# SparkFun_Digi_XBee_Explorer_USB-C.net
KiCad netlist of a schematic drawn in EAGLE
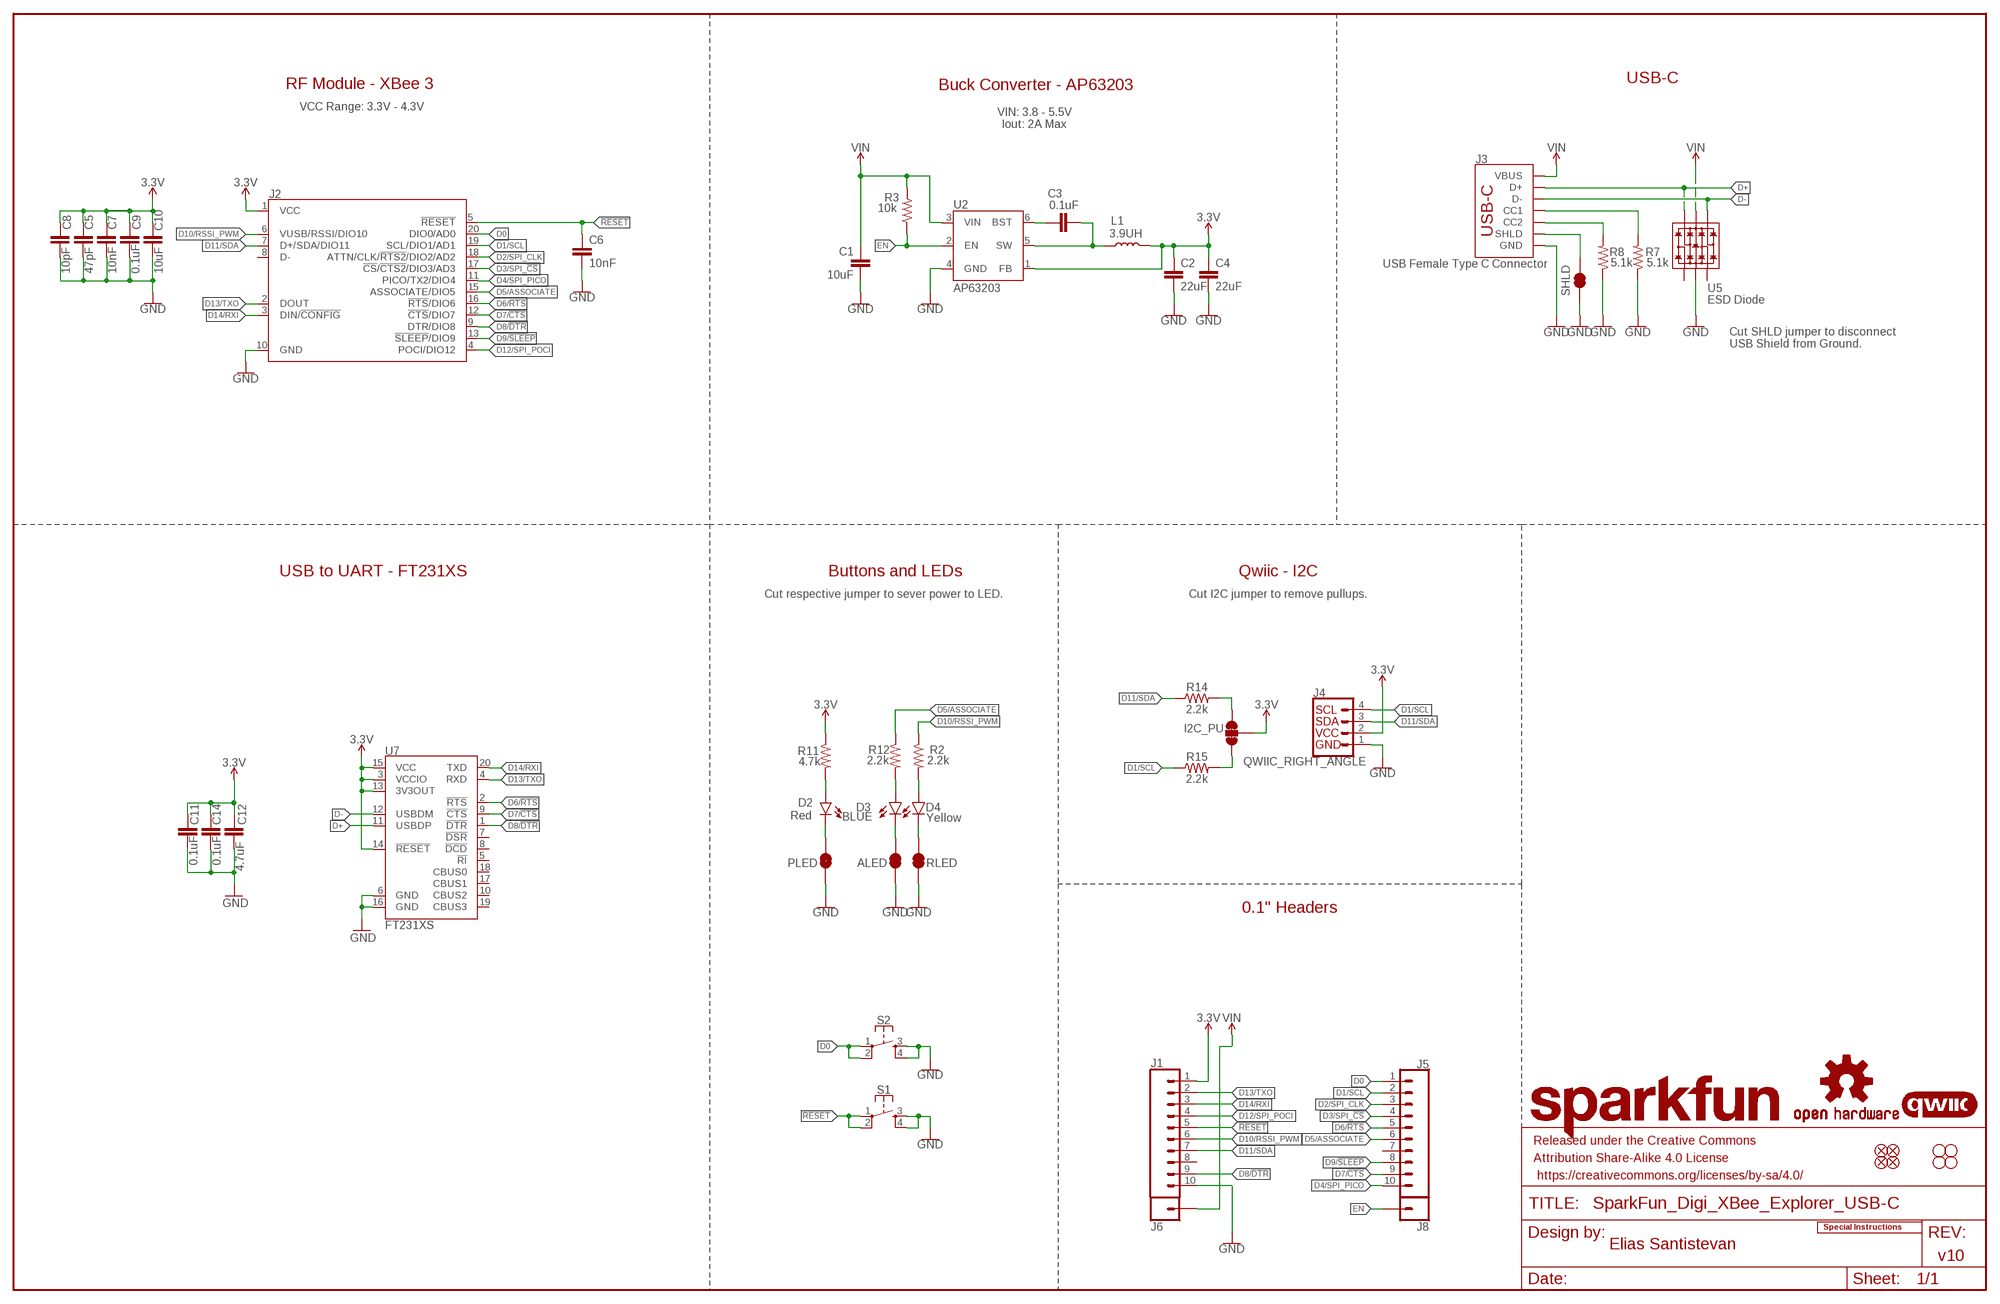
[diagram p0: schematic, sheet 1]

(export (version "E")
  (design (tool "Eeschema 10.0.6"))
  (components
    (comp (ref "ALED")
      (value "JUMPER-SMT_2_NC_TRACE_SILK")
      (footprint "eagle-import:SMT-JUMPER_2_NC_TRACE_SILK")
      (libsource (lib "eagle-import") (part "JUMPER-SMT_2_NC_TRACE_SILK"))
    )
    (comp (ref "C1")
      (value "10uF")
      (footprint "eagle-import:1210")
      (libsource (lib "eagle-import") (part "10UF-1210-50V-20%"))
    )
    (comp (ref "C2")
      (value "22uF")
      (footprint "eagle-import:0603")
      (libsource (lib "eagle-import") (part "22UF-0603-6.3V-20%"))
    )
    (comp (ref "C3")
      (value "0.1uF")
      (footprint "eagle-import:0603")
      (libsource (lib "eagle-import") (part "0.1UF-0603-25V-5%"))
    )
    (comp (ref "C4")
      (value "22uF")
      (footprint "eagle-import:0603")
      (libsource (lib "eagle-import") (part "22UF-0603-6.3V-20%"))
    )
    (comp (ref "C5")
      (value "47pF")
      (footprint "eagle-import:0603")
      (libsource (lib "eagle-import") (part "47PF-0603-50V-5%"))
    )
    (comp (ref "C6")
      (value "10nF")
      (footprint "eagle-import:0603")
      (libsource (lib "eagle-import") (part "10NF-0603-50V-10%"))
    )
    (comp (ref "C7")
      (value "10nF")
      (footprint "eagle-import:0603")
      (libsource (lib "eagle-import") (part "10NF-0603-50V-10%"))
    )
    (comp (ref "C8")
      (value "10pF")
      (footprint "eagle-import:0603")
      (libsource (lib "eagle-import") (part "10PF-0603-50V-5%"))
    )
    (comp (ref "C9")
      (value "0.1uF")
      (footprint "eagle-import:0603")
      (libsource (lib "eagle-import") (part "0.1UF-0603-25V-(+80/-20%)"))
    )
    (comp (ref "C10")
      (value "10uF")
      (footprint "eagle-import:0603")
      (libsource (lib "eagle-import") (part "10UF-0603-6.3V-20%"))
    )
    (comp (ref "C11")
      (value "0.1uF")
      (footprint "eagle-import:0603")
      (libsource (lib "eagle-import") (part "0.1UF-0603-25V-(+80/-20%)"))
    )
    (comp (ref "C12")
      (value "4.7uF")
      (footprint "eagle-import:0603")
      (libsource (lib "eagle-import") (part "4.7UF-0603-6.3V-(10%)"))
    )
    (comp (ref "C14")
      (value "0.1uF")
      (footprint "eagle-import:0603")
      (libsource (lib "eagle-import") (part "0.1UF-0603-25V-(+80/-20%)"))
    )
    (comp (ref "D2")
      (value "Red")
      (footprint "eagle-import:LED-0603")
      (libsource (lib "eagle-import") (part "LED-RED_0603-KB"))
    )
    (comp (ref "D3")
      (value "BLUE")
      (footprint "eagle-import:LED-0603")
      (libsource (lib "eagle-import") (part "LED-BLUE0603"))
    )
    (comp (ref "D4")
      (value "Yellow")
      (footprint "eagle-import:LED-0603")
      (libsource (lib "eagle-import") (part "LED-YELLOW0603"))
    )
    (comp (ref "FD1")
      (value "FIDUCIAL1X2")
      (footprint "eagle-import:FIDUCIAL-1X2")
      (libsource (lib "eagle-import") (part "FIDUCIAL1X2"))
    )
    (comp (ref "FD2")
      (value "FIDUCIAL1X2")
      (footprint "eagle-import:FIDUCIAL-1X2")
      (libsource (lib "eagle-import") (part "FIDUCIAL1X2"))
    )
    (comp (ref "FD3")
      (value "FIDUCIAL1X2")
      (footprint "eagle-import:FIDUCIAL-1X2")
      (libsource (lib "eagle-import") (part "FIDUCIAL1X2"))
    )
    (comp (ref "FD4")
      (value "FIDUCIAL1X2")
      (footprint "eagle-import:FIDUCIAL-1X2")
      (libsource (lib "eagle-import") (part "FIDUCIAL1X2"))
    )
    (comp (ref "FRAME1")
      (value "FRAME-LEDGER")
      (footprint "eagle-import:CREATIVE_COMMONS")
      (libsource (lib "eagle-import") (part "FRAME-LEDGER"))
    )
    (comp (ref "H1")
      (value "STAND-OFFTIGHT")
      (footprint "eagle-import:STAND-OFF-TIGHT")
      (libsource (lib "eagle-import") (part "STAND-OFFTIGHT"))
    )
    (comp (ref "H2")
      (value "STAND-OFFTIGHT")
      (footprint "eagle-import:STAND-OFF-TIGHT")
      (libsource (lib "eagle-import") (part "STAND-OFFTIGHT"))
    )
    (comp (ref "H3")
      (value "STAND-OFFTIGHT")
      (footprint "eagle-import:STAND-OFF-TIGHT")
      (libsource (lib "eagle-import") (part "STAND-OFFTIGHT"))
    )
    (comp (ref "H4")
      (value "STAND-OFFTIGHT")
      (footprint "eagle-import:STAND-OFF-TIGHT")
      (libsource (lib "eagle-import") (part "STAND-OFFTIGHT"))
    )
    (comp (ref "I2C_PU")
      (value "JUMPER-SMT_3_2-NC_TRACE_SILK")
      (footprint "eagle-import:SMT-JUMPER_3_2-NC_TRACE_SILK")
      (libsource (lib "eagle-import") (part "JUMPER-SMT_3_2-NC_TRACE_SILK"))
    )
    (comp (ref "J1")
      (value "CONN_01PTH_NO_SILK_STAND")
      (footprint "eagle-import:1X01_NO_SILK_STAND")
      (libsource (lib "eagle-import") (part "CONN_01PTH_NO_SILK_STAND"))
    )
    (comp (ref "J2")
      (value "XBEE_UPDATEXBEE_SMD")
      (footprint "eagle-import:XBEE3-SMD")
      (libsource (lib "eagle-import") (part "XBEE_UPDATEXBEE_SMD"))
    )
    (comp (ref "J3")
      (value "USB Female Type C Connector")
      (footprint "eagle-import:USB-C-16P-4LAYER-ISOLATED")
      (libsource (lib "eagle-import") (part "USB_C_4-LAYER-ISOLATED"))
    )
    (comp (ref "J4")
      (value "QWIIC_RIGHT_ANGLE")
      (footprint "eagle-import:JST04_1MM_RA")
      (libsource (lib "eagle-import") (part "QWIIC_CONNECTORJS-1MM"))
    )
    (comp (ref "J5")
      (value "CONN_10NO_SILK_PTH_FEMALE")
      (footprint "eagle-import:1X10_NO_SILK")
      (libsource (lib "eagle-import") (part "CONN_10NO_SILK_PTH_FEMALE"))
    )
    (comp (ref "J6")
      (value "CONN_10NO_SILK_PTH_FEMALE")
      (footprint "eagle-import:1X10_NO_SILK")
      (libsource (lib "eagle-import") (part "CONN_10NO_SILK_PTH_FEMALE"))
    )
    (comp (ref "J8")
      (value "CONN_01PTH_NO_SILK_STAND")
      (footprint "eagle-import:1X01_NO_SILK_STAND")
      (libsource (lib "eagle-import") (part "CONN_01PTH_NO_SILK_STAND"))
    )
    (comp (ref "L1")
      (value "3.9UH")
      (footprint "eagle-import:INDUCTOR_3.9UH")
      (libsource (lib "eagle-import") (part "3.9UH"))
    )
    (comp (ref "LOGO1")
      (value "SFE_LOGO_NAME.2_INCH")
      (footprint "eagle-import:SFE_LOGO_NAME_.2")
      (libsource (lib "eagle-import") (part "SFE_LOGO_NAME.2_INCH"))
    )
    (comp (ref "LOGO2")
      (value "OSHW-LOGOS")
      (footprint "eagle-import:OSHW-LOGO-S")
      (libsource (lib "eagle-import") (part "OSHW-LOGOS"))
    )
    (comp (ref "LOGO3")
      (value "QWIIC_LOGO_4MM")
      (footprint "eagle-import:QWIIC_4MM")
      (libsource (lib "eagle-import") (part "QWIIC_LOGO_4MM"))
    )
    (comp (ref "LOGO4")
      (value "SPECIAL_INSTRUCTIONS-ORDERING")
      (footprint "eagle-import:ORDERING_INSTRUCTIONS")
      (libsource (lib "eagle-import") (part "SPECIAL_INSTRUCTIONS-ORDERING"))
    )
    (comp (ref "PLED")
      (value "JUMPER-SMT_2_NC_TRACE_SILK")
      (footprint "eagle-import:SMT-JUMPER_2_NC_TRACE_SILK")
      (libsource (lib "eagle-import") (part "JUMPER-SMT_2_NC_TRACE_SILK"))
    )
    (comp (ref "R2")
      (value "2.2k")
      (footprint "eagle-import:0603")
      (libsource (lib "eagle-import") (part "2.2KOHM-0603-1/10W-1%"))
    )
    (comp (ref "R3")
      (value "10k")
      (footprint "eagle-import:0603")
      (libsource (lib "eagle-import") (part "10KOHM-0603-1/10W-1%"))
    )
    (comp (ref "R7")
      (value "5.1k")
      (footprint "eagle-import:0603")
      (libsource (lib "eagle-import") (part "5.1KOHM5.1KOHM-0603-1/10W-1%"))
    )
    (comp (ref "R8")
      (value "5.1k")
      (footprint "eagle-import:0603")
      (libsource (lib "eagle-import") (part "5.1KOHM5.1KOHM-0603-1/10W-1%"))
    )
    (comp (ref "R11")
      (value "4.7k")
      (footprint "eagle-import:0603")
      (libsource (lib "eagle-import") (part "4.7KOHM-0603-1/10W-1%"))
    )
    (comp (ref "R12")
      (value "2.2k")
      (footprint "eagle-import:0603")
      (libsource (lib "eagle-import") (part "2.2KOHM-0603-1/10W-1%"))
    )
    (comp (ref "R14")
      (value "2.2k")
      (footprint "eagle-import:0603")
      (libsource (lib "eagle-import") (part "2.2KOHM-0603-1/10W-1%"))
    )
    (comp (ref "R15")
      (value "2.2k")
      (footprint "eagle-import:0603")
      (libsource (lib "eagle-import") (part "2.2KOHM-0603-1/10W-1%"))
    )
    (comp (ref "RLED")
      (value "JUMPER-SMT_2_NC_TRACE_SILK")
      (footprint "eagle-import:SMT-JUMPER_2_NC_TRACE_SILK")
      (libsource (lib "eagle-import") (part "JUMPER-SMT_2_NC_TRACE_SILK"))
    )
    (comp (ref "S1")
      (value "MOMENTARY-SWITCH-SPST-2-SMD-5.2MM-TALL")
      (footprint "eagle-import:TACTILE_SWITCH_SMD_5.2MM")
      (libsource (lib "eagle-import") (part "MOMENTARY-SWITCH-SPST-2-SMD-5.2MM-TALL"))
    )
    (comp (ref "S2")
      (value "MOMENTARY-SWITCH-SPST-2-SMD-5.2MM-TALL")
      (footprint "eagle-import:TACTILE_SWITCH_SMD_5.2MM")
      (libsource (lib "eagle-import") (part "MOMENTARY-SWITCH-SPST-2-SMD-5.2MM-TALL"))
    )
    (comp (ref "SHLD")
      (value "JUMPER-SMT_2_NC_TRACE_SILK")
      (footprint "eagle-import:SMT-JUMPER_2_NC_TRACE_SILK")
      (libsource (lib "eagle-import") (part "JUMPER-SMT_2_NC_TRACE_SILK"))
    )
    (comp (ref "U2")
      (value "AP63203")
      (footprint "eagle-import:SOT23-6")
      (libsource (lib "eagle-import") (part "AP63203"))
    )
    (comp (ref "U5")
      (value "ESD Diode")
      (footprint "eagle-import:SOT-23-6")
      (libsource (lib "eagle-import") (part "TVS_DIODE_ARRAY_DT1042-04SO-7"))
    )
    (comp (ref "U7")
      (value "FT231XS")
      (footprint "eagle-import:SSOP20_L")
      (libsource (lib "eagle-import") (part "FT231XS"))
    )
  )
  (nets
    (net (code "1") (name "/D3{slash}SPI_~{CS}") (class "Default")
      (node (ref "J2") (pin "17") (pinfunction "~{CS}/~{CTS2}/DIO3/AD3_17") (pintype "bidirectional"))
      (node (ref "J5") (pin "4") (pinfunction "4_4") (pintype "passive"))
    )
    (net (code "2") (name "/D6{slash}~{RTS}") (class "Default")
      (node (ref "J2") (pin "16") (pinfunction "~{RTS}/DIO6_16") (pintype "input"))
      (node (ref "J5") (pin "5") (pinfunction "5_5") (pintype "passive"))
      (node (ref "U7") (pin "2") (pinfunction "~{RTS}_2") (pintype "bidirectional"))
    )
    (net (code "3") (name "/D7{slash}~{CTS}") (class "Default")
      (node (ref "J2") (pin "12") (pinfunction "~{CTS}/DIO7_12") (pintype "output"))
      (node (ref "J5") (pin "9") (pinfunction "9_9") (pintype "passive"))
      (node (ref "U7") (pin "9") (pinfunction "~{CTS}_9") (pintype "bidirectional"))
    )
    (net (code "4") (name "/D8{slash}~{DTR}") (class "Default")
      (node (ref "J2") (pin "9") (pinfunction "DTR/DIO8_9") (pintype "bidirectional"))
      (node (ref "J6") (pin "9") (pinfunction "9_9") (pintype "passive"))
      (node (ref "U7") (pin "1") (pinfunction "~{DTR}_1") (pintype "bidirectional"))
    )
    (net (code "5") (name "/D9{slash}~{SLEEP}") (class "Default")
      (node (ref "J2") (pin "13") (pinfunction "~{SLEEP}/DIO9_13") (pintype "bidirectional"))
      (node (ref "J5") (pin "8") (pinfunction "8_8") (pintype "passive"))
    )
    (net (code "6") (name "/~{RESET}") (class "Default")
      (node (ref "C6") (pin "1") (pinfunction "1_1") (pintype "passive"))
      (node (ref "J2") (pin "5") (pinfunction "~{RESET}_5") (pintype "input"))
      (node (ref "J6") (pin "5") (pinfunction "5_5") (pintype "passive"))
      (node (ref "S1") (pin "1") (pinfunction "1_1") (pintype "passive"))
      (node (ref "S1") (pin "2") (pinfunction "2_2") (pintype "passive"))
    )
    (net (code "7") (name "3.3V") (class "Default")
      (node (ref "C10") (pin "1") (pinfunction "1_1") (pintype "passive"))
      (node (ref "C11") (pin "1") (pinfunction "1_1") (pintype "passive"))
      (node (ref "C12") (pin "1") (pinfunction "1_1") (pintype "passive"))
      (node (ref "C14") (pin "1") (pinfunction "1_1") (pintype "passive"))
      (node (ref "C2") (pin "1") (pinfunction "1_1") (pintype "passive"))
      (node (ref "C4") (pin "1") (pinfunction "1_1") (pintype "passive"))
      (node (ref "C5") (pin "1") (pinfunction "1_1") (pintype "passive"))
      (node (ref "C7") (pin "1") (pinfunction "1_1") (pintype "passive"))
      (node (ref "C8") (pin "1") (pinfunction "1_1") (pintype "passive"))
      (node (ref "C9") (pin "1") (pinfunction "1_1") (pintype "passive"))
      (node (ref "I2C_PU") (pin "2") (pinfunction "2_2") (pintype "passive"))
      (node (ref "J2") (pin "1") (pinfunction "VCC_1") (pintype "power_in"))
      (node (ref "J4") (pin "2") (pinfunction "2_2") (pintype "power_in"))
      (node (ref "J6") (pin "1") (pinfunction "1_1") (pintype "passive"))
      (node (ref "L1") (pin "P$2") (pinfunction "2_P$2") (pintype "passive"))
      (node (ref "R11") (pin "1") (pinfunction "1_1") (pintype "passive"))
      (node (ref "U2") (pin "1") (pinfunction "FB_1") (pintype "bidirectional"))
      (node (ref "U7") (pin "13") (pinfunction "3V3OUT_13") (pintype "bidirectional"))
      (node (ref "U7") (pin "14") (pinfunction "~{RESET}_14") (pintype "bidirectional"))
      (node (ref "U7") (pin "15") (pinfunction "VCC_15") (pintype "bidirectional"))
      (node (ref "U7") (pin "3") (pinfunction "VCCIO_3") (pintype "bidirectional"))
    )
    (net (code "8") (name "D+") (class "Default")
      (node (ref "J3") (pin "A6") (pinfunction "D+_A6") (pintype "bidirectional"))
      (node (ref "J3") (pin "B6") (pinfunction "D+_B6") (pintype "bidirectional"))
      (node (ref "U5") (pin "6") (pinfunction "IO4_6") (pintype "bidirectional"))
      (node (ref "U7") (pin "11") (pinfunction "USBDP_11") (pintype "bidirectional"))
    )
    (net (code "9") (name "D-") (class "Default")
      (node (ref "J3") (pin "A7") (pinfunction "D-_A7") (pintype "bidirectional"))
      (node (ref "J3") (pin "B7") (pinfunction "D-_B7") (pintype "bidirectional"))
      (node (ref "U5") (pin "4") (pinfunction "IO3_4") (pintype "bidirectional"))
      (node (ref "U7") (pin "12") (pinfunction "USBDM_12") (pintype "bidirectional"))
    )
    (net (code "10") (name "D0") (class "Default")
      (node (ref "J2") (pin "20") (pinfunction "DIO0/AD0_20") (pintype "bidirectional"))
      (node (ref "J5") (pin "1") (pinfunction "1_1") (pintype "passive"))
      (node (ref "S2") (pin "1") (pinfunction "1_1") (pintype "passive"))
      (node (ref "S2") (pin "2") (pinfunction "2_2") (pintype "passive"))
    )
    (net (code "11") (name "D1{slash}SCL") (class "Default")
      (node (ref "J2") (pin "19") (pinfunction "SCL/DIO1/AD1_19") (pintype "bidirectional"))
      (node (ref "J4") (pin "4") (pinfunction "4_4") (pintype "passive"))
      (node (ref "J5") (pin "2") (pinfunction "2_2") (pintype "passive"))
      (node (ref "R15") (pin "1") (pinfunction "1_1") (pintype "passive"))
    )
    (net (code "12") (name "D2{slash}SPI_CLK") (class "Default")
      (node (ref "J2") (pin "18") (pinfunction "ATTN/CLK/~{RTS2}/DIO2/AD2_18") (pintype "bidirectional"))
      (node (ref "J5") (pin "3") (pinfunction "3_3") (pintype "passive"))
    )
    (net (code "13") (name "D4{slash}SPI_PICO") (class "Default")
      (node (ref "J2") (pin "11") (pinfunction "PICO/TX2/DIO4_11") (pintype "bidirectional"))
      (node (ref "J5") (pin "10") (pinfunction "10_10") (pintype "passive"))
    )
    (net (code "14") (name "D5{slash}ASSOCIATE") (class "Default")
      (node (ref "J2") (pin "15") (pinfunction "ASSOCIATE/DIO5_15") (pintype "bidirectional"))
      (node (ref "J5") (pin "6") (pinfunction "6_6") (pintype "passive"))
      (node (ref "R12") (pin "1") (pinfunction "1_1") (pintype "passive"))
    )
    (net (code "15") (name "D10{slash}RSSI_PWM") (class "Default")
      (node (ref "J2") (pin "6") (pinfunction "VUSB/RSSI/DIO10_6") (pintype "bidirectional"))
      (node (ref "J6") (pin "6") (pinfunction "6_6") (pintype "passive"))
      (node (ref "R2") (pin "1") (pinfunction "1_1") (pintype "passive"))
    )
    (net (code "16") (name "D11{slash}SDA") (class "Default")
      (node (ref "J2") (pin "7") (pinfunction "D+/SDA/DIO11_7") (pintype "bidirectional"))
      (node (ref "J4") (pin "3") (pinfunction "3_3") (pintype "passive"))
      (node (ref "J6") (pin "7") (pinfunction "7_7") (pintype "passive"))
      (node (ref "R14") (pin "1") (pinfunction "1_1") (pintype "passive"))
    )
    (net (code "17") (name "D12{slash}SPI_POCI") (class "Default")
      (node (ref "J2") (pin "4") (pinfunction "POCI/DIO12_4") (pintype "bidirectional"))
      (node (ref "J6") (pin "4") (pinfunction "4_4") (pintype "passive"))
    )
    (net (code "18") (name "D13{slash}TXO") (class "Default")
      (node (ref "J2") (pin "2") (pinfunction "DOUT_2") (pintype "output"))
      (node (ref "J6") (pin "2") (pinfunction "2_2") (pintype "passive"))
      (node (ref "U7") (pin "4") (pinfunction "RXD_4") (pintype "bidirectional"))
    )
    (net (code "19") (name "D14{slash}RXI") (class "Default")
      (node (ref "J2") (pin "3") (pinfunction "DIN/~{CONFIG}_3") (pintype "input"))
      (node (ref "J6") (pin "3") (pinfunction "3_3") (pintype "passive"))
      (node (ref "U7") (pin "20") (pinfunction "TXD_20") (pintype "bidirectional"))
    )
    (net (code "20") (name "EN") (class "Default")
      (node (ref "J8") (pin "1") (pinfunction "1_1") (pintype "passive"))
      (node (ref "R3") (pin "1") (pinfunction "1_1") (pintype "passive"))
      (node (ref "U2") (pin "2") (pinfunction "EN_2") (pintype "bidirectional"))
    )
    (net (code "21") (name "GND") (class "Default")
      (node (ref "ALED") (pin "1") (pinfunction "1_1") (pintype "passive"))
      (node (ref "C1") (pin "2") (pinfunction "2_2") (pintype "passive"))
      (node (ref "C10") (pin "2") (pinfunction "2_2") (pintype "passive"))
      (node (ref "C11") (pin "2") (pinfunction "2_2") (pintype "passive"))
      (node (ref "C12") (pin "2") (pinfunction "2_2") (pintype "passive"))
      (node (ref "C14") (pin "2") (pinfunction "2_2") (pintype "passive"))
      (node (ref "C2") (pin "2") (pinfunction "2_2") (pintype "passive"))
      (node (ref "C4") (pin "2") (pinfunction "2_2") (pintype "passive"))
      (node (ref "C5") (pin "2") (pinfunction "2_2") (pintype "passive"))
      (node (ref "C6") (pin "2") (pinfunction "2_2") (pintype "passive"))
      (node (ref "C7") (pin "2") (pinfunction "2_2") (pintype "passive"))
      (node (ref "C8") (pin "2") (pinfunction "2_2") (pintype "passive"))
      (node (ref "C9") (pin "2") (pinfunction "2_2") (pintype "passive"))
      (node (ref "J2") (pin "10") (pinfunction "GND_10") (pintype "power_in"))
      (node (ref "J3") (pin "GND") (pinfunction "GND_GND") (pintype "bidirectional"))
      (node (ref "J3") (pin "GND2") (pinfunction "GND_GND2") (pintype "bidirectional"))
      (node (ref "J4") (pin "1") (pinfunction "1_1") (pintype "power_in"))
      (node (ref "J6") (pin "10") (pinfunction "10_10") (pintype "passive"))
      (node (ref "PLED") (pin "1") (pinfunction "1_1") (pintype "passive"))
      (node (ref "R7") (pin "1") (pinfunction "1_1") (pintype "passive"))
      (node (ref "R8") (pin "1") (pinfunction "1_1") (pintype "passive"))
      (node (ref "RLED") (pin "1") (pinfunction "1_1") (pintype "passive"))
      (node (ref "S1") (pin "3") (pinfunction "3_3") (pintype "passive"))
      (node (ref "S1") (pin "4") (pinfunction "4_4") (pintype "passive"))
      (node (ref "S2") (pin "3") (pinfunction "3_3") (pintype "passive"))
      (node (ref "S2") (pin "4") (pinfunction "4_4") (pintype "passive"))
      (node (ref "SHLD") (pin "1") (pinfunction "1_1") (pintype "passive"))
      (node (ref "U2") (pin "4") (pinfunction "GND_4") (pintype "bidirectional"))
      (node (ref "U5") (pin "2") (pinfunction "VSS_2") (pintype "bidirectional"))
      (node (ref "U7") (pin "16") (pinfunction "GND_16") (pintype "bidirectional"))
      (node (ref "U7") (pin "6") (pinfunction "GND_6") (pintype "bidirectional"))
    )
    (net (code "22") (name "Net-(ALED-Pad2)") (class "Default")
      (node (ref "ALED") (pin "2") (pinfunction "2_2") (pintype "passive"))
      (node (ref "D3") (pin "C") (pinfunction "C_C") (pintype "passive"))
    )
    (net (code "23") (name "Net-(D2-PadA)") (class "Default")
      (node (ref "D2") (pin "A") (pinfunction "A_A") (pintype "passive"))
      (node (ref "R11") (pin "2") (pinfunction "2_2") (pintype "passive"))
    )
    (net (code "24") (name "Net-(D2-PadC)") (class "Default")
      (node (ref "D2") (pin "C") (pinfunction "C_C") (pintype "passive"))
      (node (ref "PLED") (pin "2") (pinfunction "2_2") (pintype "passive"))
    )
    (net (code "25") (name "Net-(D3-PadA)") (class "Default")
      (node (ref "D3") (pin "A") (pinfunction "A_A") (pintype "passive"))
      (node (ref "R12") (pin "2") (pinfunction "2_2") (pintype "passive"))
    )
    (net (code "26") (name "Net-(D4-PadA)") (class "Default")
      (node (ref "D4") (pin "A") (pinfunction "A_A") (pintype "passive"))
      (node (ref "R2") (pin "2") (pinfunction "2_2") (pintype "passive"))
    )
    (net (code "27") (name "Net-(D4-PadC)") (class "Default")
      (node (ref "D4") (pin "C") (pinfunction "C_C") (pintype "passive"))
      (node (ref "RLED") (pin "2") (pinfunction "2_2") (pintype "passive"))
    )
    (net (code "28") (name "Net-(I2C_PU-Pad1)") (class "Default")
      (node (ref "I2C_PU") (pin "1") (pinfunction "1_1") (pintype "passive"))
      (node (ref "R15") (pin "2") (pinfunction "2_2") (pintype "passive"))
    )
    (net (code "29") (name "Net-(I2C_PU-Pad3)") (class "Default")
      (node (ref "I2C_PU") (pin "3") (pinfunction "3_3") (pintype "passive"))
      (node (ref "R14") (pin "2") (pinfunction "2_2") (pintype "passive"))
    )
    (net (code "30") (name "Net-(J3-CC1)") (class "Default")
      (node (ref "J3") (pin "A5") (pinfunction "CC1_A5") (pintype "bidirectional"))
      (node (ref "R7") (pin "2") (pinfunction "2_2") (pintype "passive"))
    )
    (net (code "31") (name "Net-(J3-CC2)") (class "Default")
      (node (ref "J3") (pin "B5") (pinfunction "CC2_B5") (pintype "bidirectional"))
      (node (ref "R8") (pin "2") (pinfunction "2_2") (pintype "passive"))
    )
    (net (code "32") (name "Net-(J3-SHLD-PadSHLD1)") (class "Default")
      (node (ref "J3") (pin "SHLD1") (pinfunction "SHLD_SHLD1") (pintype "bidirectional"))
      (node (ref "J3") (pin "SHLD2") (pinfunction "SHLD_SHLD2") (pintype "bidirectional"))
      (node (ref "J3") (pin "SHLD3") (pinfunction "SHLD_SHLD3") (pintype "bidirectional"))
      (node (ref "J3") (pin "SHLD4") (pinfunction "SHLD_SHLD4") (pintype "bidirectional"))
      (node (ref "J3") (pin "SHLD5") (pinfunction "SHLD_SHLD5") (pintype "bidirectional"))
      (node (ref "J3") (pin "SHLD6") (pinfunction "SHLD_SHLD6") (pintype "bidirectional"))
      (node (ref "J3") (pin "SHLD7") (pinfunction "SHLD_SHLD7") (pintype "bidirectional"))
      (node (ref "J3") (pin "SHLD8") (pinfunction "SHLD_SHLD8") (pintype "bidirectional"))
      (node (ref "SHLD") (pin "2") (pinfunction "2_2") (pintype "passive"))
    )
    (net (code "33") (name "Net-(L1-1)") (class "Default")
      (node (ref "C3") (pin "2") (pinfunction "2_2") (pintype "passive"))
      (node (ref "L1") (pin "P$1") (pinfunction "1_P$1") (pintype "passive"))
      (node (ref "U2") (pin "5") (pinfunction "SW_5") (pintype "bidirectional"))
    )
    (net (code "34") (name "Net-(U2-BST)") (class "Default")
      (node (ref "C3") (pin "1") (pinfunction "1_1") (pintype "passive"))
      (node (ref "U2") (pin "6") (pinfunction "BST_6") (pintype "bidirectional"))
    )
    (net (code "35") (name "VIN") (class "Default")
      (node (ref "C1") (pin "1") (pinfunction "1_1") (pintype "passive"))
      (node (ref "J1") (pin "1") (pinfunction "1_1") (pintype "passive"))
      (node (ref "J3") (pin "VBUS1") (pinfunction "VBUS_VBUS1") (pintype "bidirectional"))
      (node (ref "J3") (pin "VBUS2") (pinfunction "VBUS_VBUS2") (pintype "bidirectional"))
      (node (ref "R3") (pin "2") (pinfunction "2_2") (pintype "passive"))
      (node (ref "U2") (pin "3") (pinfunction "VIN_3") (pintype "bidirectional"))
      (node (ref "U5") (pin "5") (pinfunction "VCC_5") (pintype "bidirectional"))
    )
    (net (code "36") (name "unconnected-(J2-D--Pad8)") (class "Default")
      (node (ref "J2") (pin "8") (pinfunction "D-_8") (pintype "bidirectional"))
    )
    (net (code "37") (name "unconnected-(J5-Pad7)") (class "Default")
      (node (ref "J5") (pin "7") (pinfunction "7_7") (pintype "passive"))
    )
    (net (code "38") (name "unconnected-(J6-Pad8)") (class "Default")
      (node (ref "J6") (pin "8") (pinfunction "8_8") (pintype "passive"))
    )
    (net (code "39") (name "unconnected-(U5-IO1-Pad1)") (class "Default")
      (node (ref "U5") (pin "1") (pinfunction "IO1_1") (pintype "bidirectional"))
    )
    (net (code "40") (name "unconnected-(U5-IO2-Pad3)") (class "Default")
      (node (ref "U5") (pin "3") (pinfunction "IO2_3") (pintype "bidirectional"))
    )
    (net (code "41") (name "unconnected-(U7-CBUS0-Pad18)") (class "Default")
      (node (ref "U7") (pin "18") (pinfunction "CBUS0_18") (pintype "bidirectional"))
    )
    (net (code "42") (name "unconnected-(U7-CBUS1-Pad17)") (class "Default")
      (node (ref "U7") (pin "17") (pinfunction "CBUS1_17") (pintype "bidirectional"))
    )
    (net (code "43") (name "unconnected-(U7-CBUS2-Pad10)") (class "Default")
      (node (ref "U7") (pin "10") (pinfunction "CBUS2_10") (pintype "bidirectional"))
    )
    (net (code "44") (name "unconnected-(U7-CBUS3-Pad19)") (class "Default")
      (node (ref "U7") (pin "19") (pinfunction "CBUS3_19") (pintype "bidirectional"))
    )
    (net (code "45") (name "unconnected-(U7-~{DCD}-Pad8)") (class "Default")
      (node (ref "U7") (pin "8") (pinfunction "~{DCD}_8") (pintype "bidirectional"))
    )
    (net (code "46") (name "unconnected-(U7-~{DSR}-Pad7)") (class "Default")
      (node (ref "U7") (pin "7") (pinfunction "~{DSR}_7") (pintype "bidirectional"))
    )
    (net (code "47") (name "unconnected-(U7-~{RI}-Pad5)") (class "Default")
      (node (ref "U7") (pin "5") (pinfunction "~{RI}_5") (pintype "bidirectional"))
    )
  )
)
